# ControlLineSelector.net
KiCad netlist of a schematic drawn in EAGLE
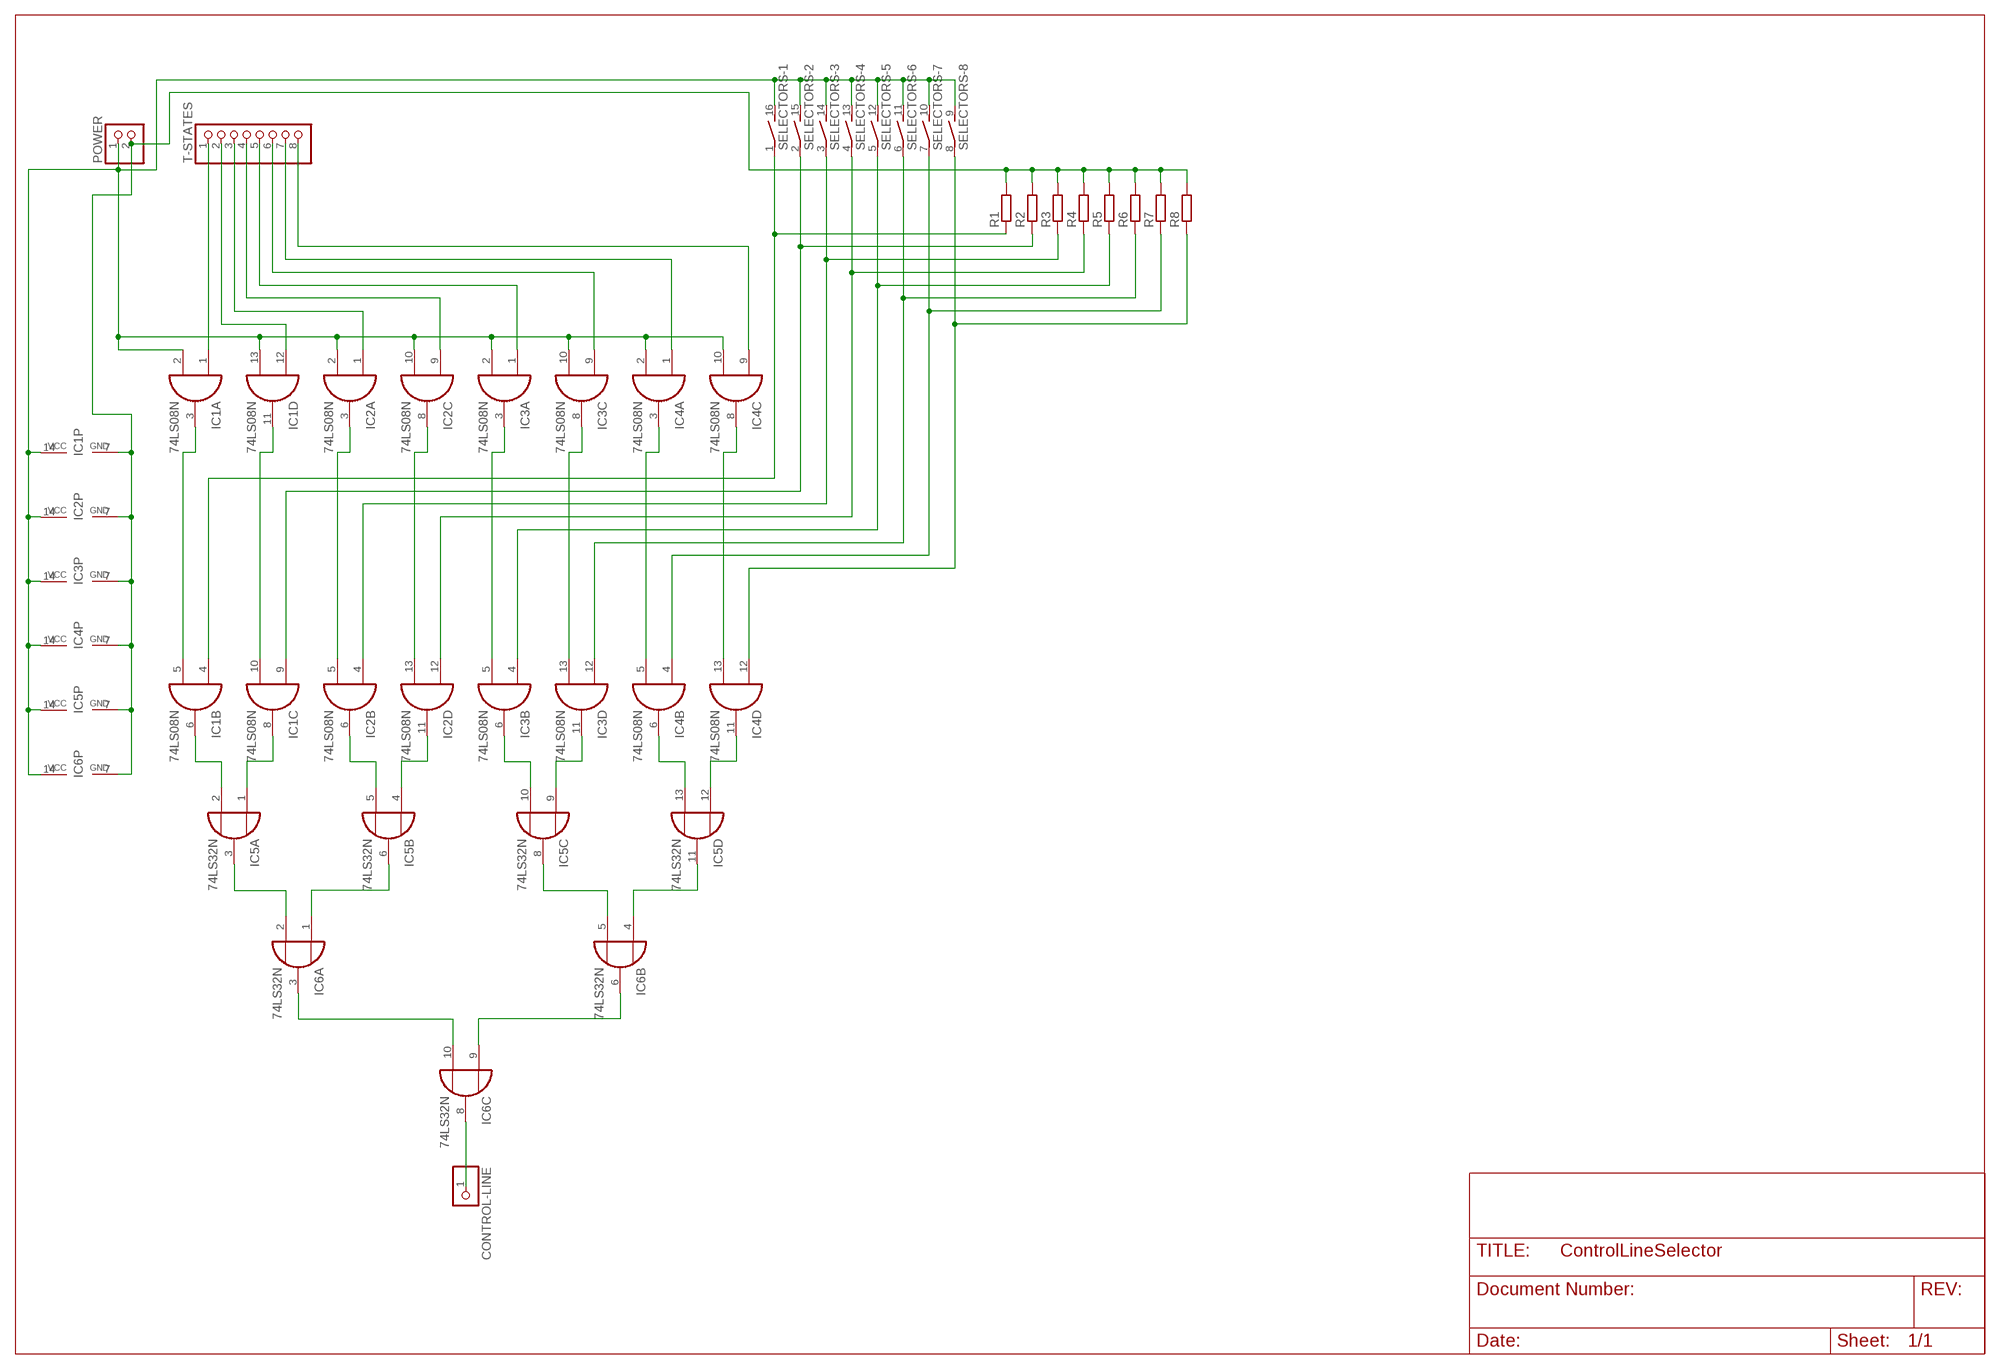
[diagram p0: schematic, sheet 1]

(export (version "E")
  (design (tool "Eeschema 10.0.6"))
  (components
    (comp (ref "CONTROL-LINE")
      (value "PINHD-1X1")
      (footprint "eagle-import:1X01")
      (libsource (lib "eagle-import") (part "PINHD-1X1"))
    )
    (comp (ref "IC1")
      (value "74LS08N")
      (footprint "eagle-import:DIL14")
      (libsource (lib "eagle-import") (part "7408NLS"))
    )
    (comp (ref "IC2")
      (value "74LS08N")
      (footprint "eagle-import:DIL14")
      (libsource (lib "eagle-import") (part "7408NLS"))
    )
    (comp (ref "IC3")
      (value "74LS08N")
      (footprint "eagle-import:DIL14")
      (libsource (lib "eagle-import") (part "7408NLS"))
    )
    (comp (ref "IC4")
      (value "74LS08N")
      (footprint "eagle-import:DIL14")
      (libsource (lib "eagle-import") (part "7408NLS"))
    )
    (comp (ref "IC5")
      (value "74LS32N")
      (footprint "eagle-import:DIL14")
      (libsource (lib "eagle-import") (part "7432NLS"))
    )
    (comp (ref "IC6")
      (value "74LS32N")
      (footprint "eagle-import:DIL14")
      (libsource (lib "eagle-import") (part "7432NLS"))
    )
    (comp (ref "POWER")
      (value "PINHD-1X2")
      (footprint "eagle-import:1X02")
      (libsource (lib "eagle-import") (part "PINHD-1X2"))
    )
    (comp (ref "R1")
      (value "R-EU_0207/7")
      (footprint "eagle-import:0207_7")
      (libsource (lib "eagle-import") (part "R-EU_0207/7"))
    )
    (comp (ref "R2")
      (value "R-EU_0207/7")
      (footprint "eagle-import:0207_7")
      (libsource (lib "eagle-import") (part "R-EU_0207/7"))
    )
    (comp (ref "R3")
      (value "R-EU_0207/7")
      (footprint "eagle-import:0207_7")
      (libsource (lib "eagle-import") (part "R-EU_0207/7"))
    )
    (comp (ref "R4")
      (value "R-EU_0207/7")
      (footprint "eagle-import:0207_7")
      (libsource (lib "eagle-import") (part "R-EU_0207/7"))
    )
    (comp (ref "R5")
      (value "R-EU_0207/7")
      (footprint "eagle-import:0207_7")
      (libsource (lib "eagle-import") (part "R-EU_0207/7"))
    )
    (comp (ref "R6")
      (value "R-EU_0207/7")
      (footprint "eagle-import:0207_7")
      (libsource (lib "eagle-import") (part "R-EU_0207/7"))
    )
    (comp (ref "R7")
      (value "R-EU_0207/7")
      (footprint "eagle-import:0207_7")
      (libsource (lib "eagle-import") (part "R-EU_0207/7"))
    )
    (comp (ref "R8")
      (value "R-EU_0207/7")
      (footprint "eagle-import:0207_7")
      (libsource (lib "eagle-import") (part "R-EU_0207/7"))
    )
    (comp (ref "SELECTORS")
      (value "DIP08S")
      (footprint "eagle-import:DIP08S")
      (libsource (lib "eagle-import") (part "DIP08S"))
    )
    (comp (ref "T-STATES")
      (value "PINHD-1X8")
      (footprint "eagle-import:1X08")
      (libsource (lib "eagle-import") (part "PINHD-1X8"))
    )
  )
  (nets
    (net (code "1") (name "Net-(IC1A-I0)") (class "Default")
      (node (ref "IC1") (pin "1") (pinfunction "I0_1") (pintype "input"))
      (node (ref "T-STATES") (pin "1") (pinfunction "1_1") (pintype "passive"))
    )
    (net (code "2") (name "Net-(IC1A-I1)") (class "Default")
      (node (ref "IC1") (pin "13") (pinfunction "I1_13") (pintype "input"))
      (node (ref "IC1") (pin "14") (pinfunction "VCC_14") (pintype "power_in"))
      (node (ref "IC1") (pin "2") (pinfunction "I1_2") (pintype "input"))
      (node (ref "IC2") (pin "10") (pinfunction "I1_10") (pintype "input"))
      (node (ref "IC2") (pin "14") (pinfunction "VCC_14") (pintype "power_in"))
      (node (ref "IC2") (pin "2") (pinfunction "I1_2") (pintype "input"))
      (node (ref "IC3") (pin "10") (pinfunction "I1_10") (pintype "input"))
      (node (ref "IC3") (pin "14") (pinfunction "VCC_14") (pintype "power_in"))
      (node (ref "IC3") (pin "2") (pinfunction "I1_2") (pintype "input"))
      (node (ref "IC4") (pin "10") (pinfunction "I1_10") (pintype "input"))
      (node (ref "IC4") (pin "14") (pinfunction "VCC_14") (pintype "power_in"))
      (node (ref "IC4") (pin "2") (pinfunction "I1_2") (pintype "input"))
      (node (ref "IC5") (pin "14") (pinfunction "VCC_14") (pintype "power_in"))
      (node (ref "IC6") (pin "14") (pinfunction "VCC_14") (pintype "power_in"))
      (node (ref "POWER") (pin "1") (pinfunction "1_1") (pintype "passive"))
      (node (ref "SELECTORS") (pin "10") (pinfunction "2_10") (pintype "passive"))
      (node (ref "SELECTORS") (pin "11") (pinfunction "2_11") (pintype "passive"))
      (node (ref "SELECTORS") (pin "12") (pinfunction "2_12") (pintype "passive"))
      (node (ref "SELECTORS") (pin "13") (pinfunction "2_13") (pintype "passive"))
      (node (ref "SELECTORS") (pin "14") (pinfunction "2_14") (pintype "passive"))
      (node (ref "SELECTORS") (pin "15") (pinfunction "2_15") (pintype "passive"))
      (node (ref "SELECTORS") (pin "16") (pinfunction "2_16") (pintype "passive"))
      (node (ref "SELECTORS") (pin "9") (pinfunction "2_9") (pintype "passive"))
    )
    (net (code "3") (name "Net-(IC1A-O)") (class "Default")
      (node (ref "IC1") (pin "3") (pinfunction "O_3") (pintype "output"))
      (node (ref "IC1") (pin "5") (pinfunction "I1_5") (pintype "input"))
    )
    (net (code "4") (name "Net-(IC1B-I0)") (class "Default")
      (node (ref "IC1") (pin "4") (pinfunction "I0_4") (pintype "input"))
      (node (ref "R1") (pin "1") (pinfunction "1_1") (pintype "passive"))
      (node (ref "SELECTORS") (pin "1") (pinfunction "1_1") (pintype "passive"))
    )
    (net (code "5") (name "Net-(IC1B-O)") (class "Default")
      (node (ref "IC1") (pin "6") (pinfunction "O_6") (pintype "output"))
      (node (ref "IC5") (pin "2") (pinfunction "I1_2") (pintype "input"))
    )
    (net (code "6") (name "Net-(IC1C-I0)") (class "Default")
      (node (ref "IC1") (pin "9") (pinfunction "I0_9") (pintype "input"))
      (node (ref "R2") (pin "1") (pinfunction "1_1") (pintype "passive"))
      (node (ref "SELECTORS") (pin "2") (pinfunction "1_2") (pintype "passive"))
    )
    (net (code "7") (name "Net-(IC1C-I1)") (class "Default")
      (node (ref "IC1") (pin "10") (pinfunction "I1_10") (pintype "input"))
      (node (ref "IC1") (pin "11") (pinfunction "O_11") (pintype "output"))
    )
    (net (code "8") (name "Net-(IC1C-O)") (class "Default")
      (node (ref "IC1") (pin "8") (pinfunction "O_8") (pintype "output"))
      (node (ref "IC5") (pin "1") (pinfunction "I0_1") (pintype "input"))
    )
    (net (code "9") (name "Net-(IC1D-I0)") (class "Default")
      (node (ref "IC1") (pin "12") (pinfunction "I0_12") (pintype "input"))
      (node (ref "T-STATES") (pin "2") (pinfunction "2_2") (pintype "passive"))
    )
    (net (code "10") (name "Net-(IC1E-GND)") (class "Default")
      (node (ref "IC1") (pin "7") (pinfunction "GND_7") (pintype "power_in"))
      (node (ref "IC2") (pin "7") (pinfunction "GND_7") (pintype "power_in"))
      (node (ref "IC3") (pin "7") (pinfunction "GND_7") (pintype "power_in"))
      (node (ref "IC4") (pin "7") (pinfunction "GND_7") (pintype "power_in"))
      (node (ref "IC5") (pin "7") (pinfunction "GND_7") (pintype "power_in"))
      (node (ref "IC6") (pin "7") (pinfunction "GND_7") (pintype "power_in"))
      (node (ref "POWER") (pin "2") (pinfunction "2_2") (pintype "passive"))
      (node (ref "R1") (pin "2") (pinfunction "2_2") (pintype "passive"))
      (node (ref "R2") (pin "2") (pinfunction "2_2") (pintype "passive"))
      (node (ref "R3") (pin "2") (pinfunction "2_2") (pintype "passive"))
      (node (ref "R4") (pin "2") (pinfunction "2_2") (pintype "passive"))
      (node (ref "R5") (pin "2") (pinfunction "2_2") (pintype "passive"))
      (node (ref "R6") (pin "2") (pinfunction "2_2") (pintype "passive"))
      (node (ref "R7") (pin "2") (pinfunction "2_2") (pintype "passive"))
      (node (ref "R8") (pin "2") (pinfunction "2_2") (pintype "passive"))
    )
    (net (code "11") (name "Net-(IC2A-I0)") (class "Default")
      (node (ref "IC2") (pin "1") (pinfunction "I0_1") (pintype "input"))
      (node (ref "T-STATES") (pin "3") (pinfunction "3_3") (pintype "passive"))
    )
    (net (code "12") (name "Net-(IC2A-O)") (class "Default")
      (node (ref "IC2") (pin "3") (pinfunction "O_3") (pintype "output"))
      (node (ref "IC2") (pin "5") (pinfunction "I1_5") (pintype "input"))
    )
    (net (code "13") (name "Net-(IC2B-I0)") (class "Default")
      (node (ref "IC2") (pin "4") (pinfunction "I0_4") (pintype "input"))
      (node (ref "R3") (pin "1") (pinfunction "1_1") (pintype "passive"))
      (node (ref "SELECTORS") (pin "3") (pinfunction "1_3") (pintype "passive"))
    )
    (net (code "14") (name "Net-(IC2B-O)") (class "Default")
      (node (ref "IC2") (pin "6") (pinfunction "O_6") (pintype "output"))
      (node (ref "IC5") (pin "5") (pinfunction "I1_5") (pintype "input"))
    )
    (net (code "15") (name "Net-(IC2C-I0)") (class "Default")
      (node (ref "IC2") (pin "9") (pinfunction "I0_9") (pintype "input"))
      (node (ref "T-STATES") (pin "4") (pinfunction "4_4") (pintype "passive"))
    )
    (net (code "16") (name "Net-(IC2C-O)") (class "Default")
      (node (ref "IC2") (pin "13") (pinfunction "I1_13") (pintype "input"))
      (node (ref "IC2") (pin "8") (pinfunction "O_8") (pintype "output"))
    )
    (net (code "17") (name "Net-(IC2D-I0)") (class "Default")
      (node (ref "IC2") (pin "12") (pinfunction "I0_12") (pintype "input"))
      (node (ref "R4") (pin "1") (pinfunction "1_1") (pintype "passive"))
      (node (ref "SELECTORS") (pin "4") (pinfunction "1_4") (pintype "passive"))
    )
    (net (code "18") (name "Net-(IC2D-O)") (class "Default")
      (node (ref "IC2") (pin "11") (pinfunction "O_11") (pintype "output"))
      (node (ref "IC5") (pin "4") (pinfunction "I0_4") (pintype "input"))
    )
    (net (code "19") (name "Net-(IC3A-I0)") (class "Default")
      (node (ref "IC3") (pin "1") (pinfunction "I0_1") (pintype "input"))
      (node (ref "T-STATES") (pin "5") (pinfunction "5_5") (pintype "passive"))
    )
    (net (code "20") (name "Net-(IC3A-O)") (class "Default")
      (node (ref "IC3") (pin "3") (pinfunction "O_3") (pintype "output"))
      (node (ref "IC3") (pin "5") (pinfunction "I1_5") (pintype "input"))
    )
    (net (code "21") (name "Net-(IC3B-I0)") (class "Default")
      (node (ref "IC3") (pin "4") (pinfunction "I0_4") (pintype "input"))
      (node (ref "R5") (pin "1") (pinfunction "1_1") (pintype "passive"))
      (node (ref "SELECTORS") (pin "5") (pinfunction "1_5") (pintype "passive"))
    )
    (net (code "22") (name "Net-(IC3B-O)") (class "Default")
      (node (ref "IC3") (pin "6") (pinfunction "O_6") (pintype "output"))
      (node (ref "IC5") (pin "10") (pinfunction "I1_10") (pintype "input"))
    )
    (net (code "23") (name "Net-(IC3C-I0)") (class "Default")
      (node (ref "IC3") (pin "9") (pinfunction "I0_9") (pintype "input"))
      (node (ref "T-STATES") (pin "6") (pinfunction "6_6") (pintype "passive"))
    )
    (net (code "24") (name "Net-(IC3C-O)") (class "Default")
      (node (ref "IC3") (pin "13") (pinfunction "I1_13") (pintype "input"))
      (node (ref "IC3") (pin "8") (pinfunction "O_8") (pintype "output"))
    )
    (net (code "25") (name "Net-(IC3D-I0)") (class "Default")
      (node (ref "IC3") (pin "12") (pinfunction "I0_12") (pintype "input"))
      (node (ref "R6") (pin "1") (pinfunction "1_1") (pintype "passive"))
      (node (ref "SELECTORS") (pin "6") (pinfunction "1_6") (pintype "passive"))
    )
    (net (code "26") (name "Net-(IC3D-O)") (class "Default")
      (node (ref "IC3") (pin "11") (pinfunction "O_11") (pintype "output"))
      (node (ref "IC5") (pin "9") (pinfunction "I0_9") (pintype "input"))
    )
    (net (code "27") (name "Net-(IC4A-I0)") (class "Default")
      (node (ref "IC4") (pin "1") (pinfunction "I0_1") (pintype "input"))
      (node (ref "T-STATES") (pin "7") (pinfunction "7_7") (pintype "passive"))
    )
    (net (code "28") (name "Net-(IC4A-O)") (class "Default")
      (node (ref "IC4") (pin "3") (pinfunction "O_3") (pintype "output"))
      (node (ref "IC4") (pin "5") (pinfunction "I1_5") (pintype "input"))
    )
    (net (code "29") (name "Net-(IC4B-I0)") (class "Default")
      (node (ref "IC4") (pin "4") (pinfunction "I0_4") (pintype "input"))
      (node (ref "R7") (pin "1") (pinfunction "1_1") (pintype "passive"))
      (node (ref "SELECTORS") (pin "7") (pinfunction "1_7") (pintype "passive"))
    )
    (net (code "30") (name "Net-(IC4B-O)") (class "Default")
      (node (ref "IC4") (pin "6") (pinfunction "O_6") (pintype "output"))
      (node (ref "IC5") (pin "13") (pinfunction "I1_13") (pintype "input"))
    )
    (net (code "31") (name "Net-(IC4C-I0)") (class "Default")
      (node (ref "IC4") (pin "9") (pinfunction "I0_9") (pintype "input"))
      (node (ref "T-STATES") (pin "8") (pinfunction "8_8") (pintype "passive"))
    )
    (net (code "32") (name "Net-(IC4C-O)") (class "Default")
      (node (ref "IC4") (pin "13") (pinfunction "I1_13") (pintype "input"))
      (node (ref "IC4") (pin "8") (pinfunction "O_8") (pintype "output"))
    )
    (net (code "33") (name "Net-(IC4D-I0)") (class "Default")
      (node (ref "IC4") (pin "12") (pinfunction "I0_12") (pintype "input"))
      (node (ref "R8") (pin "1") (pinfunction "1_1") (pintype "passive"))
      (node (ref "SELECTORS") (pin "8") (pinfunction "1_8") (pintype "passive"))
    )
    (net (code "34") (name "Net-(IC4D-O)") (class "Default")
      (node (ref "IC4") (pin "11") (pinfunction "O_11") (pintype "output"))
      (node (ref "IC5") (pin "12") (pinfunction "I0_12") (pintype "input"))
    )
    (net (code "35") (name "Net-(IC5A-O)") (class "Default")
      (node (ref "IC5") (pin "3") (pinfunction "O_3") (pintype "output"))
      (node (ref "IC6") (pin "2") (pinfunction "I1_2") (pintype "input"))
    )
    (net (code "36") (name "Net-(IC5B-O)") (class "Default")
      (node (ref "IC5") (pin "6") (pinfunction "O_6") (pintype "output"))
      (node (ref "IC6") (pin "1") (pinfunction "I0_1") (pintype "input"))
    )
    (net (code "37") (name "Net-(IC5C-O)") (class "Default")
      (node (ref "IC5") (pin "8") (pinfunction "O_8") (pintype "output"))
      (node (ref "IC6") (pin "5") (pinfunction "I1_5") (pintype "input"))
    )
    (net (code "38") (name "Net-(IC5D-O)") (class "Default")
      (node (ref "IC5") (pin "11") (pinfunction "O_11") (pintype "output"))
      (node (ref "IC6") (pin "4") (pinfunction "I0_4") (pintype "input"))
    )
    (net (code "39") (name "Net-(IC6A-O)") (class "Default")
      (node (ref "IC6") (pin "10") (pinfunction "I1_10") (pintype "input"))
      (node (ref "IC6") (pin "3") (pinfunction "O_3") (pintype "output"))
    )
    (net (code "40") (name "Net-(IC6B-O)") (class "Default")
      (node (ref "IC6") (pin "6") (pinfunction "O_6") (pintype "output"))
      (node (ref "IC6") (pin "9") (pinfunction "I0_9") (pintype "input"))
    )
    (net (code "41") (name "Net-(IC6C-O)") (class "Default")
      (node (ref "CONTROL-LINE") (pin "1") (pinfunction "1_1") (pintype "passive"))
      (node (ref "IC6") (pin "8") (pinfunction "O_8") (pintype "output"))
    )
  )
)
